# Audio_Input_Mic_In.net
KiCad netlist of a schematic drawn in Altium Designer
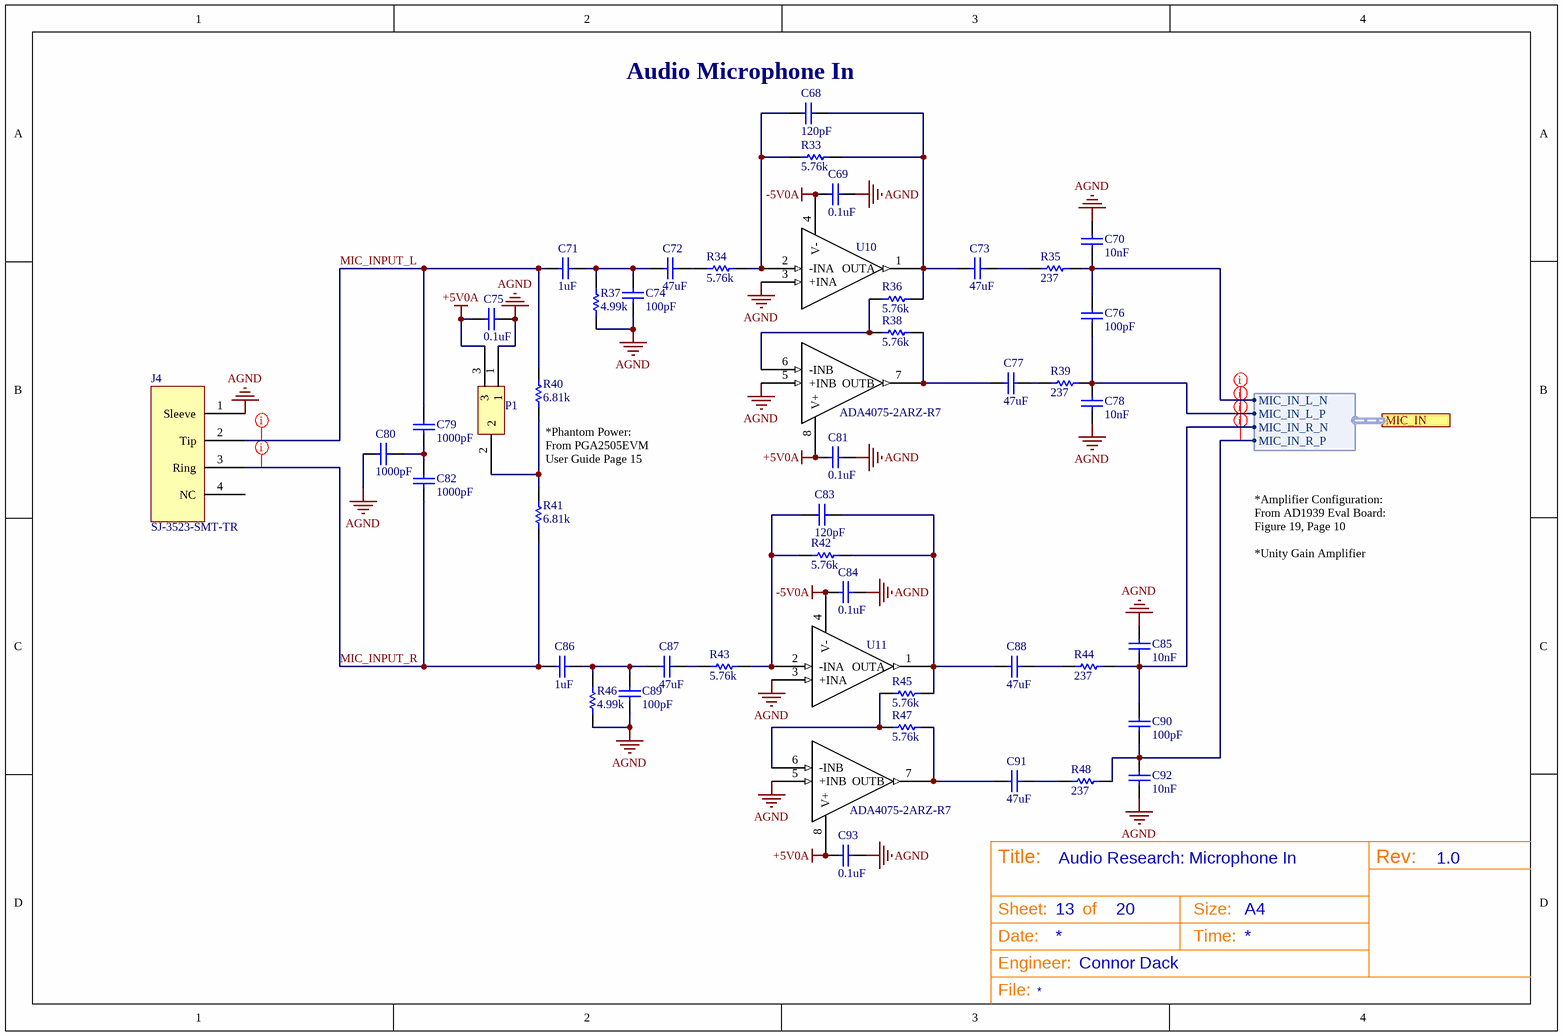
[diagram p0: Audio_Input_Mic_In.SchDoc]

(export (version "E")
  (design (tool "Eeschema 10.0.6"))
  (components
    (comp (ref "C68")
      (value "CL10C121JB8NCNC")
      (footprint "3-0603_L")
      (description "120pF 50V Ceramic Capacitor C0G, NP0 0603 (1608 Metric) 0.063\" L x 0.031\" W (1.60mm x 0.80mm)")
      (fields
        (field (name "MANUFACTURER") "Samsung Electro-Mechanics America, Inc.")
        (field (name "TOLERANCE") "±5%")
        (field (name "CAPACITANCE") "120pF")
      )
      (libsource (lib "Schematic_Components") (part "CL10C121JB8NCNC"))
    )
    (comp (ref "C69")
      (value "CL10F104ZO8NNNC")
      (footprint "3-0603_L")
      (description "CAP CER 0.1UF 16V Y5V 0603")
      (fields
        (field (name "MANUFACTURER") "Samsung")
        (field (name "TOLERANCE") "80%")
        (field (name "CAPACITANCE") "0.1uF")
      )
      (libsource (lib "Schematic_Components_CD") (part "CL10F104ZO8NNNC"))
    )
    (comp (ref "C70")
      (value "~")
      (footprint "3-0603_L")
      (description "CAP CER 10000PF 200V X7R 0603")
      (fields
        (field (name "MANUFACTURER") "KEMET")
        (field (name "MANUFACTURER PART NUMBER") "C0603C103J2RACTU")
        (field (name "CAPACITANCE") "10nF")
      )
      (libsource (lib "Miscellaneous Devices") (part "C0603C103J2RACTU"))
    )
    (comp (ref "C71")
      (value "CGA3E1X7R1C105M080AC")
      (footprint "3-0603_L")
      (description "CAP CER 1UF 16V X7R 0603")
      (fields
        (field (name "MANUFACTURER") "TDK")
        (field (name "TOLERANCE") "20%")
        (field (name "CAPACITANCE") "1uF")
      )
      (libsource (lib "Schematic_Components_CD") (part "CGA3E1X7R1C105M080AC"))
    )
    (comp (ref "C72")
      (value "CL32A476KOJNNNE")
      (footprint "C1210X25_L")
      (description "CAP CER 47UF 16V X5R 1210")
      (fields
        (field (name "MANUFACTURER") "Samsung")
        (field (name "TOLERANCE") "10%")
        (field (name "CAPACITANCE") "47uF")
      )
      (libsource (lib "Schematic_Components_CD") (part "CL32A476KOJNNNE"))
    )
    (comp (ref "C73")
      (value "CL32A476KOJNNNE")
      (footprint "C1210X25_L")
      (description "CAP CER 47UF 16V X5R 1210")
      (fields
        (field (name "MANUFACTURER") "Samsung")
        (field (name "TOLERANCE") "10%")
        (field (name "CAPACITANCE") "47uF")
      )
      (libsource (lib "Schematic_Components_CD") (part "CL32A476KOJNNNE"))
    )
    (comp (ref "C74")
      (value "C1608C0G2A101J")
      (footprint "3-0603_L")
      (description "CAP CER 100PF 100V 5% NP0 0603")
      (fields
        (field (name "MANUFACTURER") "TDK Corporation")
        (field (name "TOLERANCE") "±5%")
        (field (name "CAPACITANCE") "100pF")
      )
      (libsource (lib "Schematic_Components") (part "C1608C0G2A101J"))
    )
    (comp (ref "C75")
      (value "CL10F104ZO8NNNC")
      (footprint "3-0603_L")
      (description "CAP CER 0.1UF 16V Y5V 0603")
      (fields
        (field (name "MANUFACTURER") "Samsung")
        (field (name "TOLERANCE") "80%")
        (field (name "CAPACITANCE") "0.1uF")
      )
      (libsource (lib "Schematic_Components_CD") (part "CL10F104ZO8NNNC"))
    )
    (comp (ref "C76")
      (value "C1608C0G2A101J")
      (footprint "3-0603_L")
      (description "CAP CER 100PF 100V 5% NP0 0603")
      (fields
        (field (name "MANUFACTURER") "TDK Corporation")
        (field (name "TOLERANCE") "±5%")
        (field (name "CAPACITANCE") "100pF")
      )
      (libsource (lib "Schematic_Components") (part "C1608C0G2A101J"))
    )
    (comp (ref "C77")
      (value "CL32A476KOJNNNE")
      (footprint "C1210X25_L")
      (description "CAP CER 47UF 16V X5R 1210")
      (fields
        (field (name "MANUFACTURER") "Samsung")
        (field (name "TOLERANCE") "10%")
        (field (name "CAPACITANCE") "47uF")
      )
      (libsource (lib "Schematic_Components_CD") (part "CL32A476KOJNNNE"))
    )
    (comp (ref "C78")
      (value "~")
      (footprint "3-0603_L")
      (description "CAP CER 10000PF 200V X7R 0603")
      (fields
        (field (name "MANUFACTURER") "KEMET")
        (field (name "MANUFACTURER PART NUMBER") "C0603C103J2RACTU")
        (field (name "CAPACITANCE") "10nF")
      )
      (libsource (lib "Miscellaneous Devices") (part "C0603C103J2RACTU"))
    )
    (comp (ref "C79")
      (value "CL10B102KB8NNNC")
      (footprint "3-0603_L")
      (description "1000pF 50V Ceramic Capacitor X7R 0603 (1608 Metric) 0.063\" L x 0.031\" W (1.60mm x 0.80mm)")
      (fields
        (field (name "MANUFACTURER") "Samsung Electro-Mechanics America, Inc.")
        (field (name "TOLERANCE") "±10%")
        (field (name "CAPACITANCE") "1000pF")
      )
      (libsource (lib "Schematic_Components") (part "CL10B102KB8NNNC"))
    )
    (comp (ref "C80")
      (value "CL10B102KB8NNNC")
      (footprint "3-0603_L")
      (description "1000pF 50V Ceramic Capacitor X7R 0603 (1608 Metric) 0.063\" L x 0.031\" W (1.60mm x 0.80mm)")
      (fields
        (field (name "MANUFACTURER") "Samsung Electro-Mechanics America, Inc.")
        (field (name "TOLERANCE") "±10%")
        (field (name "CAPACITANCE") "1000pF")
      )
      (libsource (lib "Schematic_Components") (part "CL10B102KB8NNNC"))
    )
    (comp (ref "C81")
      (value "CL10F104ZO8NNNC")
      (footprint "3-0603_L")
      (description "CAP CER 0.1UF 16V Y5V 0603")
      (fields
        (field (name "MANUFACTURER") "Samsung")
        (field (name "TOLERANCE") "80%")
        (field (name "CAPACITANCE") "0.1uF")
      )
      (libsource (lib "Schematic_Components_CD") (part "CL10F104ZO8NNNC"))
    )
    (comp (ref "C82")
      (value "CL10B102KB8NNNC")
      (footprint "3-0603_L")
      (description "1000pF 50V Ceramic Capacitor X7R 0603 (1608 Metric) 0.063\" L x 0.031\" W (1.60mm x 0.80mm)")
      (fields
        (field (name "MANUFACTURER") "Samsung Electro-Mechanics America, Inc.")
        (field (name "TOLERANCE") "±10%")
        (field (name "CAPACITANCE") "1000pF")
      )
      (libsource (lib "Schematic_Components") (part "CL10B102KB8NNNC"))
    )
    (comp (ref "C83")
      (value "CL10C121JB8NCNC")
      (footprint "3-0603_L")
      (description "120pF 50V Ceramic Capacitor C0G, NP0 0603 (1608 Metric) 0.063\" L x 0.031\" W (1.60mm x 0.80mm)")
      (fields
        (field (name "MANUFACTURER") "Samsung Electro-Mechanics America, Inc.")
        (field (name "TOLERANCE") "±5%")
        (field (name "CAPACITANCE") "120pF")
      )
      (libsource (lib "Schematic_Components") (part "CL10C121JB8NCNC"))
    )
    (comp (ref "C84")
      (value "CL10F104ZO8NNNC")
      (footprint "3-0603_L")
      (description "CAP CER 0.1UF 16V Y5V 0603")
      (fields
        (field (name "MANUFACTURER") "Samsung")
        (field (name "TOLERANCE") "80%")
        (field (name "CAPACITANCE") "0.1uF")
      )
      (libsource (lib "Schematic_Components_CD") (part "CL10F104ZO8NNNC"))
    )
    (comp (ref "C85")
      (value "~")
      (footprint "3-0603_L")
      (description "CAP CER 10000PF 200V X7R 0603")
      (fields
        (field (name "MANUFACTURER") "KEMET")
        (field (name "MANUFACTURER PART NUMBER") "C0603C103J2RACTU")
        (field (name "CAPACITANCE") "10nF")
      )
      (libsource (lib "Miscellaneous Devices") (part "C0603C103J2RACTU"))
    )
    (comp (ref "C86")
      (value "CGA3E1X7R1C105M080AC")
      (footprint "3-0603_L")
      (description "CAP CER 1UF 16V X7R 0603")
      (fields
        (field (name "MANUFACTURER") "TDK")
        (field (name "TOLERANCE") "20%")
        (field (name "CAPACITANCE") "1uF")
      )
      (libsource (lib "Schematic_Components_CD") (part "CGA3E1X7R1C105M080AC"))
    )
    (comp (ref "C87")
      (value "CL32A476KOJNNNE")
      (footprint "C1210X25_L")
      (description "CAP CER 47UF 16V X5R 1210")
      (fields
        (field (name "MANUFACTURER") "Samsung")
        (field (name "TOLERANCE") "10%")
        (field (name "CAPACITANCE") "47uF")
      )
      (libsource (lib "Schematic_Components_CD") (part "CL32A476KOJNNNE"))
    )
    (comp (ref "C88")
      (value "CL32A476KOJNNNE")
      (footprint "C1210X25_L")
      (description "CAP CER 47UF 16V X5R 1210")
      (fields
        (field (name "MANUFACTURER") "Samsung")
        (field (name "TOLERANCE") "10%")
        (field (name "CAPACITANCE") "47uF")
      )
      (libsource (lib "Schematic_Components_CD") (part "CL32A476KOJNNNE"))
    )
    (comp (ref "C89")
      (value "C1608C0G2A101J")
      (footprint "3-0603_L")
      (description "CAP CER 100PF 100V 5% NP0 0603")
      (fields
        (field (name "MANUFACTURER") "TDK Corporation")
        (field (name "TOLERANCE") "±5%")
        (field (name "CAPACITANCE") "100pF")
      )
      (libsource (lib "Schematic_Components") (part "C1608C0G2A101J"))
    )
    (comp (ref "C90")
      (value "C1608C0G2A101J")
      (footprint "3-0603_L")
      (description "CAP CER 100PF 100V 5% NP0 0603")
      (fields
        (field (name "MANUFACTURER") "TDK Corporation")
        (field (name "TOLERANCE") "±5%")
        (field (name "CAPACITANCE") "100pF")
      )
      (libsource (lib "Schematic_Components") (part "C1608C0G2A101J"))
    )
    (comp (ref "C91")
      (value "CL32A476KOJNNNE")
      (footprint "C1210X25_L")
      (description "CAP CER 47UF 16V X5R 1210")
      (fields
        (field (name "MANUFACTURER") "Samsung")
        (field (name "TOLERANCE") "10%")
        (field (name "CAPACITANCE") "47uF")
      )
      (libsource (lib "Schematic_Components_CD") (part "CL32A476KOJNNNE"))
    )
    (comp (ref "C92")
      (value "~")
      (footprint "3-0603_L")
      (description "CAP CER 10000PF 200V X7R 0603")
      (fields
        (field (name "MANUFACTURER") "KEMET")
        (field (name "MANUFACTURER PART NUMBER") "C0603C103J2RACTU")
        (field (name "CAPACITANCE") "10nF")
      )
      (libsource (lib "Miscellaneous Devices") (part "C0603C103J2RACTU"))
    )
    (comp (ref "C93")
      (value "CL10F104ZO8NNNC")
      (footprint "3-0603_L")
      (description "CAP CER 0.1UF 16V Y5V 0603")
      (fields
        (field (name "MANUFACTURER") "Samsung")
        (field (name "TOLERANCE") "80%")
        (field (name "CAPACITANCE") "0.1uF")
      )
      (libsource (lib "Schematic_Components_CD") (part "CL10F104ZO8NNNC"))
    )
    (comp (ref "J4")
      (value "SJ-3523-SMT-TR")
      (footprint "SJ-3523-SMT-TR")
      (description "3.50mm (0.141\", 1/8\", Mini Plug) - Headphone Phone Jack Stereo Connector Solder")
      (fields
        (field (name "MANUFACTURER") "CUI Inc.")
        (field (name "MANUFACTURER PART NUMBER") "SJ-3523-SMT-TR")
        (field (name "PUBLISHER") "Altium Limited")
      )
      (libsource (lib "NIH_DE0_Nano_Daughter_Card_Library") (part "SJ-3523-SMT-TR"))
    )
    (comp (ref "P1")
      (value "3PIN_Connector")
      (footprint "3Pin_Header")
      (description "3 Pin Through Hole Connector with 0.1\" Spacing")
      (fields
        (field (name "MANUFACTURER") "Samtec")
        (field (name "MANUFACTURER PART NUMBER") "TSW-103-07-G-S")
        (field (name "PUBLISHER") "Altium Limited")
      )
      (libsource (lib "Schematic_Components_CD") (part "CONN_TH_3PIN_0D1"))
    )
    (comp (ref "R33")
      (value "ERJ-3EKF5761V")
      (footprint "3-0603_R_L")
      (description "RES SMD 5.76K OHM 1% 1/10W 0603")
      (fields
        (field (name "MANUFACTURER") "Panasonic Electronic Components")
        (field (name "TOLERANCE") "±1%")
        (field (name "RESISTANCE (OHMS)") "5.76k")
      )
      (libsource (lib "Schematic_Components") (part "ERJ-3EKF5761V"))
    )
    (comp (ref "R34")
      (value "ERJ-3EKF5761V")
      (footprint "3-0603_R_L")
      (description "RES SMD 5.76K OHM 1% 1/10W 0603")
      (fields
        (field (name "MANUFACTURER") "Panasonic Electronic Components")
        (field (name "TOLERANCE") "±1%")
        (field (name "RESISTANCE (OHMS)") "5.76k")
      )
      (libsource (lib "Schematic_Components") (part "ERJ-3EKF5761V"))
    )
    (comp (ref "R35")
      (value "ERJ-3EKF2370V")
      (footprint "3-0603_R_L")
      (description "RES SMD 237 OHM 1% 1/10W 0603")
      (fields
        (field (name "MANUFACTURER") "Panasonic Electronic Components")
        (field (name "TOLERANCE") "±1%")
        (field (name "RESISTANCE (OHMS)") "237")
      )
      (libsource (lib "Schematic_Components") (part "ERJ-3EKF2370V"))
    )
    (comp (ref "R36")
      (value "ERJ-3EKF5761V")
      (footprint "3-0603_R_L")
      (description "RES SMD 5.76K OHM 1% 1/10W 0603")
      (fields
        (field (name "MANUFACTURER") "Panasonic Electronic Components")
        (field (name "TOLERANCE") "±1%")
        (field (name "RESISTANCE (OHMS)") "5.76k")
      )
      (libsource (lib "Schematic_Components") (part "ERJ-3EKF5761V"))
    )
    (comp (ref "R37")
      (value "ERJ-3EKF4991V")
      (footprint "3-0603_R_L")
      (description "RES SMD 4.99K OHM 1% 1/10W 0603")
      (fields
        (field (name "MANUFACTURER") "Panasonic Electronic Components")
        (field (name "TOLERANCE") "±1%")
        (field (name "RESISTANCE (OHMS)") "4.99k")
      )
      (libsource (lib "Schematic_Components") (part "ERJ-3EKF4991V"))
    )
    (comp (ref "R38")
      (value "ERJ-3EKF5761V")
      (footprint "3-0603_R_L")
      (description "RES SMD 5.76K OHM 1% 1/10W 0603")
      (fields
        (field (name "MANUFACTURER") "Panasonic Electronic Components")
        (field (name "TOLERANCE") "±1%")
        (field (name "RESISTANCE (OHMS)") "5.76k")
      )
      (libsource (lib "Schematic_Components") (part "ERJ-3EKF5761V"))
    )
    (comp (ref "R39")
      (value "ERJ-3EKF2370V")
      (footprint "3-0603_R_L")
      (description "RES SMD 237 OHM 1% 1/10W 0603")
      (fields
        (field (name "MANUFACTURER") "Panasonic Electronic Components")
        (field (name "TOLERANCE") "±1%")
        (field (name "RESISTANCE (OHMS)") "237")
      )
      (libsource (lib "Schematic_Components") (part "ERJ-3EKF2370V"))
    )
    (comp (ref "R40")
      (value "ERJ-3EKF6811V")
      (footprint "3-0603_R_L")
      (description "RES SMD 6.81K OHM 1% 1/10W 0603")
      (fields
        (field (name "MANUFACTURER") "Panasonic ECG")
        (field (name "TOLERANCE") "1%")
        (field (name "RESISTANCE") "6.81k")
      )
      (libsource (lib "Schematic_Components_CD") (part "ERJ-3EKF6811V"))
    )
    (comp (ref "R41")
      (value "ERJ-3EKF6811V")
      (footprint "3-0603_R_L")
      (description "RES SMD 6.81K OHM 1% 1/10W 0603")
      (fields
        (field (name "MANUFACTURER") "Panasonic ECG")
        (field (name "TOLERANCE") "1%")
        (field (name "RESISTANCE") "6.81k")
      )
      (libsource (lib "Schematic_Components_CD") (part "ERJ-3EKF6811V"))
    )
    (comp (ref "R42")
      (value "ERJ-3EKF5761V")
      (footprint "3-0603_R_L")
      (description "RES SMD 5.76K OHM 1% 1/10W 0603")
      (fields
        (field (name "MANUFACTURER") "Panasonic Electronic Components")
        (field (name "TOLERANCE") "±1%")
        (field (name "RESISTANCE (OHMS)") "5.76k")
      )
      (libsource (lib "Schematic_Components") (part "ERJ-3EKF5761V"))
    )
    (comp (ref "R43")
      (value "ERJ-3EKF5761V")
      (footprint "3-0603_R_L")
      (description "RES SMD 5.76K OHM 1% 1/10W 0603")
      (fields
        (field (name "MANUFACTURER") "Panasonic Electronic Components")
        (field (name "TOLERANCE") "±1%")
        (field (name "RESISTANCE (OHMS)") "5.76k")
      )
      (libsource (lib "Schematic_Components") (part "ERJ-3EKF5761V"))
    )
    (comp (ref "R44")
      (value "ERJ-3EKF2370V")
      (footprint "3-0603_R_L")
      (description "RES SMD 237 OHM 1% 1/10W 0603")
      (fields
        (field (name "MANUFACTURER") "Panasonic Electronic Components")
        (field (name "TOLERANCE") "±1%")
        (field (name "RESISTANCE (OHMS)") "237")
      )
      (libsource (lib "Schematic_Components") (part "ERJ-3EKF2370V"))
    )
    (comp (ref "R45")
      (value "ERJ-3EKF5761V")
      (footprint "3-0603_R_L")
      (description "RES SMD 5.76K OHM 1% 1/10W 0603")
      (fields
        (field (name "MANUFACTURER") "Panasonic Electronic Components")
        (field (name "TOLERANCE") "±1%")
        (field (name "RESISTANCE (OHMS)") "5.76k")
      )
      (libsource (lib "Schematic_Components") (part "ERJ-3EKF5761V"))
    )
    (comp (ref "R46")
      (value "ERJ-3EKF4991V")
      (footprint "3-0603_R_L")
      (description "RES SMD 4.99K OHM 1% 1/10W 0603")
      (fields
        (field (name "MANUFACTURER") "Panasonic Electronic Components")
        (field (name "TOLERANCE") "±1%")
        (field (name "RESISTANCE (OHMS)") "4.99k")
      )
      (libsource (lib "Schematic_Components") (part "ERJ-3EKF4991V"))
    )
    (comp (ref "R47")
      (value "ERJ-3EKF5761V")
      (footprint "3-0603_R_L")
      (description "RES SMD 5.76K OHM 1% 1/10W 0603")
      (fields
        (field (name "MANUFACTURER") "Panasonic Electronic Components")
        (field (name "TOLERANCE") "±1%")
        (field (name "RESISTANCE (OHMS)") "5.76k")
      )
      (libsource (lib "Schematic_Components") (part "ERJ-3EKF5761V"))
    )
    (comp (ref "R48")
      (value "ERJ-3EKF2370V")
      (footprint "3-0603_R_L")
      (description "RES SMD 237 OHM 1% 1/10W 0603")
      (fields
        (field (name "MANUFACTURER") "Panasonic Electronic Components")
        (field (name "TOLERANCE") "±1%")
        (field (name "RESISTANCE (OHMS)") "237")
      )
      (libsource (lib "Schematic_Components") (part "ERJ-3EKF2370V"))
    )
    (comp (ref "U10")
      (value "ADA4075-2ARZ-R7")
      (footprint "SOIC127P600X175-8L")
      (description "IC OPAMP GP 6.5MHZ 8SOIC")
      (fields
        (field (name "MANUFACTURER") "Analog Devices Inc.")
        (field (name "MANUFACTURER PART NUMBER") "ADA4075-2ARZ-R7")
      )
      (libsource (lib "Schematic_Components_CD") (part "ADA4075-2ARZ-R7"))
    )
    (comp (ref "U11")
      (value "ADA4075-2ARZ-R7")
      (footprint "SOIC127P600X175-8L")
      (description "IC OPAMP GP 6.5MHZ 8SOIC")
      (fields
        (field (name "MANUFACTURER") "Analog Devices Inc.")
        (field (name "MANUFACTURER PART NUMBER") "ADA4075-2ARZ-R7")
      )
      (libsource (lib "Schematic_Components_CD") (part "ADA4075-2ARZ-R7"))
    )
  )
  (nets
    (net (code "2") (name "+5V0A") (class "Default")
      (node (ref "C75") (pin "2") (pinfunction "2_2") (pintype "passive"))
      (node (ref "C81") (pin "2") (pinfunction "2_2") (pintype "passive"))
      (node (ref "C93") (pin "2") (pinfunction "2_2") (pintype "passive"))
      (node (ref "P1") (pin "3") (pinfunction "3_3") (pintype "passive"))
      (node (ref "U10") (pin "8") (pinfunction "V+_8") (pintype "passive"))
      (node (ref "U11") (pin "8") (pinfunction "V+_8") (pintype "passive"))
    )
    (net (code "3") (name "-5V0A") (class "Default")
      (node (ref "C69") (pin "2") (pinfunction "2_2") (pintype "passive"))
      (node (ref "C84") (pin "2") (pinfunction "2_2") (pintype "passive"))
      (node (ref "U10") (pin "4") (pinfunction "V-_4") (pintype "passive"))
      (node (ref "U11") (pin "4") (pinfunction "V-_4") (pintype "passive"))
    )
    (net (code "4") (name "/MIC_INPUT_L") (class "Default")
      (node (ref "C71") (pin "1") (pinfunction "1_1") (pintype "passive"))
      (node (ref "C79") (pin "2") (pinfunction "2_2") (pintype "passive"))
      (node (ref "J4") (pin "2") (pinfunction "Tip_2") (pintype "passive"))
      (node (ref "R40") (pin "2") (pinfunction "2_2") (pintype "passive"))
    )
    (net (code "5") (name "/MIC_INPUT_R") (class "Default")
      (node (ref "C82") (pin "1") (pinfunction "1_1") (pintype "passive"))
      (node (ref "C86") (pin "1") (pinfunction "1_1") (pintype "passive"))
      (node (ref "J4") (pin "3") (pinfunction "Ring_3") (pintype "passive"))
      (node (ref "R41") (pin "1") (pinfunction "1_1") (pintype "passive"))
    )
    (net (code "7") (name "AGND") (class "Default")
      (node (ref "C69") (pin "1") (pinfunction "1_1") (pintype "passive"))
      (node (ref "C70") (pin "2") (pinfunction "2_2") (pintype "passive"))
      (node (ref "C74") (pin "2") (pinfunction "2_2") (pintype "passive"))
      (node (ref "C75") (pin "1") (pinfunction "1_1") (pintype "passive"))
      (node (ref "C78") (pin "1") (pinfunction "1_1") (pintype "passive"))
      (node (ref "C80") (pin "2") (pinfunction "2_2") (pintype "passive"))
      (node (ref "C81") (pin "1") (pinfunction "1_1") (pintype "passive"))
      (node (ref "C84") (pin "1") (pinfunction "1_1") (pintype "passive"))
      (node (ref "C85") (pin "2") (pinfunction "2_2") (pintype "passive"))
      (node (ref "C89") (pin "2") (pinfunction "2_2") (pintype "passive"))
      (node (ref "C92") (pin "1") (pinfunction "1_1") (pintype "passive"))
      (node (ref "C93") (pin "1") (pinfunction "1_1") (pintype "passive"))
      (node (ref "J4") (pin "1") (pinfunction "Sleeve_1") (pintype "passive"))
      (node (ref "P1") (pin "1") (pinfunction "1_1") (pintype "passive"))
      (node (ref "R37") (pin "1") (pinfunction "1_1") (pintype "passive"))
      (node (ref "R46") (pin "1") (pinfunction "1_1") (pintype "passive"))
      (node (ref "U10") (pin "3") (pinfunction "+INA_3") (pintype "input"))
      (node (ref "U10") (pin "5") (pinfunction "+INB_5") (pintype "input"))
      (node (ref "U11") (pin "3") (pinfunction "+INA_3") (pintype "input"))
      (node (ref "U11") (pin "5") (pinfunction "+INB_5") (pintype "input"))
    )
    (net (code "8") (name "Net-(C70-Pad1)") (class "Default")
      (node (ref "C70") (pin "1") (pinfunction "1_1") (pintype "passive"))
      (node (ref "C76") (pin "2") (pinfunction "2_2") (pintype "passive"))
      (node (ref "R35") (pin "2") (pinfunction "2_2") (pintype "passive"))
    )
    (net (code "9") (name "Net-(C71-Pad2)") (class "Default")
      (node (ref "C71") (pin "2") (pinfunction "2_2") (pintype "passive"))
      (node (ref "C72") (pin "1") (pinfunction "1_1") (pintype "passive"))
      (node (ref "C74") (pin "1") (pinfunction "1_1") (pintype "passive"))
      (node (ref "R37") (pin "2") (pinfunction "2_2") (pintype "passive"))
    )
    (net (code "10") (name "Net-(C72-Pad2)") (class "Default")
      (node (ref "C72") (pin "2") (pinfunction "2_2") (pintype "passive"))
      (node (ref "R34") (pin "1") (pinfunction "1_1") (pintype "passive"))
    )
    (net (code "11") (name "Net-(C73-Pad2)") (class "Default")
      (node (ref "C73") (pin "2") (pinfunction "2_2") (pintype "passive"))
      (node (ref "R35") (pin "1") (pinfunction "1_1") (pintype "passive"))
    )
    (net (code "12") (name "Net-(C76-Pad1)") (class "Default")
      (node (ref "C76") (pin "1") (pinfunction "1_1") (pintype "passive"))
      (node (ref "C78") (pin "2") (pinfunction "2_2") (pintype "passive"))
      (node (ref "R39") (pin "2") (pinfunction "2_2") (pintype "passive"))
    )
    (net (code "13") (name "Net-(C77-Pad2)") (class "Default")
      (node (ref "C77") (pin "2") (pinfunction "2_2") (pintype "passive"))
      (node (ref "R39") (pin "1") (pinfunction "1_1") (pintype "passive"))
    )
    (net (code "14") (name "Net-(C79-Pad1)") (class "Default")
      (node (ref "C79") (pin "1") (pinfunction "1_1") (pintype "passive"))
      (node (ref "C80") (pin "1") (pinfunction "1_1") (pintype "passive"))
      (node (ref "C82") (pin "2") (pinfunction "2_2") (pintype "passive"))
    )
    (net (code "15") (name "Net-(C85-Pad1)") (class "Default")
      (node (ref "C85") (pin "1") (pinfunction "1_1") (pintype "passive"))
      (node (ref "C90") (pin "2") (pinfunction "2_2") (pintype "passive"))
      (node (ref "R44") (pin "2") (pinfunction "2_2") (pintype "passive"))
    )
    (net (code "16") (name "Net-(C86-Pad2)") (class "Default")
      (node (ref "C86") (pin "2") (pinfunction "2_2") (pintype "passive"))
      (node (ref "C87") (pin "1") (pinfunction "1_1") (pintype "passive"))
      (node (ref "C89") (pin "1") (pinfunction "1_1") (pintype "passive"))
      (node (ref "R46") (pin "2") (pinfunction "2_2") (pintype "passive"))
    )
    (net (code "17") (name "Net-(C87-Pad2)") (class "Default")
      (node (ref "C87") (pin "2") (pinfunction "2_2") (pintype "passive"))
      (node (ref "R43") (pin "1") (pinfunction "1_1") (pintype "passive"))
    )
    (net (code "18") (name "Net-(C88-Pad2)") (class "Default")
      (node (ref "C88") (pin "2") (pinfunction "2_2") (pintype "passive"))
      (node (ref "R44") (pin "1") (pinfunction "1_1") (pintype "passive"))
    )
    (net (code "19") (name "Net-(C90-Pad1)") (class "Default")
      (node (ref "C90") (pin "1") (pinfunction "1_1") (pintype "passive"))
      (node (ref "C92") (pin "2") (pinfunction "2_2") (pintype "passive"))
      (node (ref "R48") (pin "2") (pinfunction "2_2") (pintype "passive"))
    )
    (net (code "20") (name "Net-(C91-Pad2)") (class "Default")
      (node (ref "C91") (pin "2") (pinfunction "2_2") (pintype "passive"))
      (node (ref "R48") (pin "1") (pinfunction "1_1") (pintype "passive"))
    )
    (net (code "21") (name "Net-(P1-Pad2)") (class "Default")
      (node (ref "P1") (pin "2") (pinfunction "2_2") (pintype "passive"))
      (node (ref "R40") (pin "1") (pinfunction "1_1") (pintype "passive"))
      (node (ref "R41") (pin "2") (pinfunction "2_2") (pintype "passive"))
    )
    (net (code "22") (name "Net-(U10--INA)") (class "Default")
      (node (ref "C68") (pin "1") (pinfunction "1_1") (pintype "passive"))
      (node (ref "R33") (pin "1") (pinfunction "1_1") (pintype "passive"))
      (node (ref "R34") (pin "2") (pinfunction "2_2") (pintype "passive"))
      (node (ref "U10") (pin "2") (pinfunction "-INA_2") (pintype "input"))
    )
    (net (code "23") (name "Net-(U10--INB)") (class "Default")
      (node (ref "R36") (pin "2") (pinfunction "2_2") (pintype "passive"))
      (node (ref "R38") (pin "1") (pinfunction "1_1") (pintype "passive"))
      (node (ref "U10") (pin "6") (pinfunction "-INB_6") (pintype "input"))
    )
    (net (code "24") (name "Net-(U10-OUTA)") (class "Default")
      (node (ref "C68") (pin "2") (pinfunction "2_2") (pintype "passive"))
      (node (ref "C73") (pin "1") (pinfunction "1_1") (pintype "passive"))
      (node (ref "R33") (pin "2") (pinfunction "2_2") (pintype "passive"))
      (node (ref "R36") (pin "1") (pinfunction "1_1") (pintype "passive"))
      (node (ref "U10") (pin "1") (pinfunction "OUTA_1") (pintype "output"))
    )
    (net (code "25") (name "Net-(U10-OUTB)") (class "Default")
      (node (ref "C77") (pin "1") (pinfunction "1_1") (pintype "passive"))
      (node (ref "R38") (pin "2") (pinfunction "2_2") (pintype "passive"))
      (node (ref "U10") (pin "7") (pinfunction "OUTB_7") (pintype "output"))
    )
    (net (code "26") (name "Net-(U11--INA)") (class "Default")
      (node (ref "C83") (pin "1") (pinfunction "1_1") (pintype "passive"))
      (node (ref "R42") (pin "1") (pinfunction "1_1") (pintype "passive"))
      (node (ref "R43") (pin "2") (pinfunction "2_2") (pintype "passive"))
      (node (ref "U11") (pin "2") (pinfunction "-INA_2") (pintype "input"))
    )
    (net (code "27") (name "Net-(U11--INB)") (class "Default")
      (node (ref "R45") (pin "2") (pinfunction "2_2") (pintype "passive"))
      (node (ref "R47") (pin "1") (pinfunction "1_1") (pintype "passive"))
      (node (ref "U11") (pin "6") (pinfunction "-INB_6") (pintype "input"))
    )
    (net (code "28") (name "Net-(U11-OUTA)") (class "Default")
      (node (ref "C83") (pin "2") (pinfunction "2_2") (pintype "passive"))
      (node (ref "C88") (pin "1") (pinfunction "1_1") (pintype "passive"))
      (node (ref "R42") (pin "2") (pinfunction "2_2") (pintype "passive"))
      (node (ref "R45") (pin "1") (pinfunction "1_1") (pintype "passive"))
      (node (ref "U11") (pin "1") (pinfunction "OUTA_1") (pintype "output"))
    )
    (net (code "29") (name "Net-(U11-OUTB)") (class "Default")
      (node (ref "C91") (pin "1") (pinfunction "1_1") (pintype "passive"))
      (node (ref "R47") (pin "2") (pinfunction "2_2") (pintype "passive"))
      (node (ref "U11") (pin "7") (pinfunction "OUTB_7") (pintype "output"))
    )
    (net (code "30") (name "unconnected-(J4-NC-Pad4)") (class "Default")
      (node (ref "J4") (pin "4") (pinfunction "NC_4") (pintype "passive"))
    )
  )
)
